# IO4-Turtle.net
KiCad netlist of a schematic drawn in EAGLE
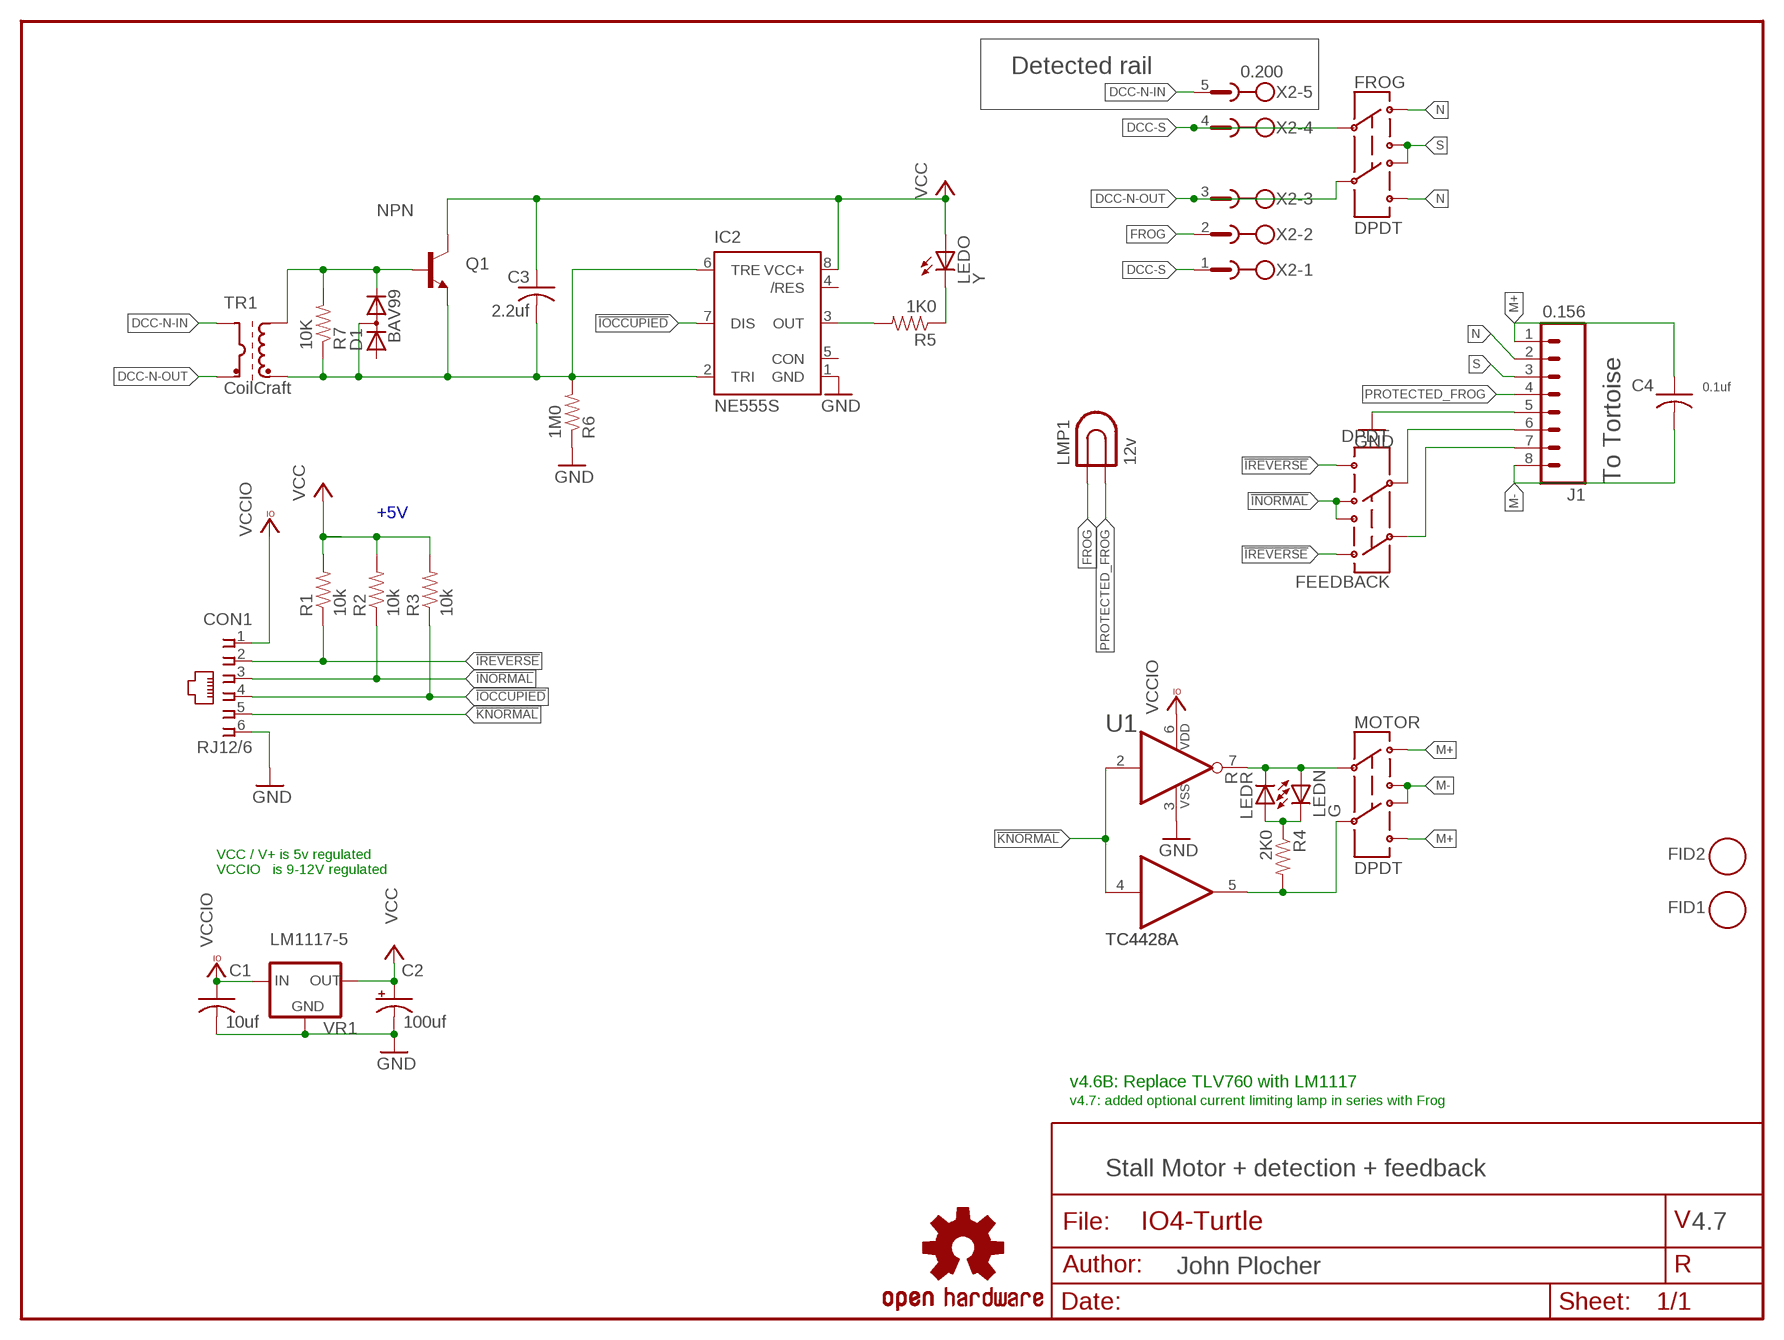
[diagram p0: schematic, sheet 1]

(export (version "E")
  (design (tool "Eeschema 10.0.6"))
  (components
    (comp (ref "C1")
      (value "10uf")
      (footprint "eagle-import:0603-CAP")
      (libsource (lib "eagle-import") (part "CAP0603"))
    )
    (comp (ref "C2")
      (value "100uf")
      (footprint "eagle-import:PANASONIC_D")
      (libsource (lib "eagle-import") (part "CAP-POLD"))
    )
    (comp (ref "C3")
      (value "2.2uf")
      (footprint "eagle-import:0603-CAP")
      (libsource (lib "eagle-import") (part "CAP0603"))
    )
    (comp (ref "C4")
      (value "0.1uf")
      (footprint "eagle-import:0805-CAP")
      (libsource (lib "eagle-import") (part "CAP0805"))
    )
    (comp (ref "CON1")
      (value "RJ12/6")
      (footprint "eagle-import:RJ25-INVERTED")
      (libsource (lib "eagle-import") (part "CONNECTOR-RJ25-43860-2-MOLEX"))
    )
    (comp (ref "D1")
      (value "BAV99")
      (footprint "eagle-import:SOT23")
      (libsource (lib "eagle-import") (part "DIODE-BAV199"))
    )
    (comp (ref "FEEDBACK")
      (value "DPDT")
      (footprint "eagle-import:8X8-SQ-PB")
      (libsource (lib "eagle-import") (part "SWITCH-DPDTPTH-PB"))
    )
    (comp (ref "FID1")
      (value "FIDUCIAL")
      (footprint "eagle-import:FIDUCIAL_1MM")
      (libsource (lib "eagle-import") (part "FIDUCIAL"))
    )
    (comp (ref "FID2")
      (value "FIDUCIAL")
      (footprint "eagle-import:FIDUCIAL_1MM")
      (libsource (lib "eagle-import") (part "FIDUCIAL"))
    )
    (comp (ref "FROG")
      (value "DPDT")
      (footprint "eagle-import:8X8-SQ-PB")
      (libsource (lib "eagle-import") (part "SWITCH-DPDTPTH-PB"))
    )
    (comp (ref "IC1")
      (value "TC4428A")
      (footprint "eagle-import:SO-08")
      (libsource (lib "eagle-import") (part "TC4428ASOICCOA"))
    )
    (comp (ref "IC2")
      (value "NE555S")
      (footprint "eagle-import:SO08")
      (libsource (lib "eagle-import") (part "NE555D"))
    )
    (comp (ref "J1")
      (value "0.156")
      (footprint "eagle-import:KK-156-8-F")
      (libsource (lib "eagle-import") (part "CONNECTOR-M081.56-F"))
    )
    (comp (ref "LEDN")
      (value "G")
      (footprint "eagle-import:0603-LED")
      (libsource (lib "eagle-import") (part "LED0603-LED"))
    )
    (comp (ref "LEDO")
      (value "Y")
      (footprint "eagle-import:0603-LED")
      (libsource (lib "eagle-import") (part "LED0603-LED"))
    )
    (comp (ref "LEDR")
      (value "R")
      (footprint "eagle-import:0603-LED")
      (libsource (lib "eagle-import") (part "LED0603-LED"))
    )
    (comp (ref "LMP1")
      (value "12v")
      (footprint "eagle-import:BULB-3156")
      (libsource (lib "eagle-import") (part "LAMPBULB"))
    )
    (comp (ref "MOTOR")
      (value "DPDT")
      (footprint "eagle-import:8X8-SQ-PB")
      (libsource (lib "eagle-import") (part "SWITCH-DPDTPTH-PB"))
    )
    (comp (ref "OSHW1")
      (value "OSHW")
      (footprint "eagle-import:OSHW-LOGO-M")
      (libsource (lib "eagle-import") (part "DOC-OSHW-LOGO-M"))
    )
    (comp (ref "Q1")
      (value "NPN")
      (footprint "eagle-import:SOT23")
      (libsource (lib "eagle-import") (part "NPN-SOT23"))
    )
    (comp (ref "R1")
      (value "10k")
      (footprint "eagle-import:0603-RES")
      (libsource (lib "eagle-import") (part "R0603-RES"))
    )
    (comp (ref "R2")
      (value "10k")
      (footprint "eagle-import:0603-RES")
      (libsource (lib "eagle-import") (part "R0603-RES"))
    )
    (comp (ref "R3")
      (value "10k")
      (footprint "eagle-import:0603-RES")
      (libsource (lib "eagle-import") (part "R0603-RES"))
    )
    (comp (ref "R4")
      (value "2K0")
      (footprint "eagle-import:0603-RES")
      (libsource (lib "eagle-import") (part "R0603-RES"))
    )
    (comp (ref "R5")
      (value "1K0")
      (footprint "eagle-import:0603-RES")
      (libsource (lib "eagle-import") (part "R0603-RES"))
    )
    (comp (ref "R6")
      (value "1M0")
      (footprint "eagle-import:0603-RES")
      (libsource (lib "eagle-import") (part "R0603-RES"))
    )
    (comp (ref "R7")
      (value "10K")
      (footprint "eagle-import:0603-RES")
      (libsource (lib "eagle-import") (part "R0603-RES"))
    )
    (comp (ref "TR1")
      (value "CoilCraft")
      (footprint "eagle-import:TH-T4")
      (libsource (lib "eagle-import") (part "PULSE-TRANSFORMERPTH"))
    )
    (comp (ref "VR1")
      (value "LM1117-5")
      (footprint "eagle-import:SOT223")
      (libsource (lib "eagle-import") (part "VREG-?-GOI5"))
    )
    (comp (ref "X2")
      (value "0.200")
      (footprint "eagle-import:MSTBA5")
      (fields (field (name "MPN") "1757271"))
      (libsource (lib "eagle-import") (part "MSTBA5"))
    )
  )
  (nets
    (net (code "1") (name "/~{INORMAL}") (class "Default")
      (node (ref "CON1") (pin "3") (pinfunction "3_3") (pintype "passive"))
      (node (ref "FEEDBACK") (pin "1B") (pinfunction "1B_1B") (pintype "bidirectional"))
      (node (ref "FEEDBACK") (pin "2A") (pinfunction "2A_2A") (pintype "bidirectional"))
      (node (ref "R2") (pin "1") (pinfunction "1_1") (pintype "passive"))
    )
    (net (code "2") (name "/~{IOCCUPIED}") (class "Default")
      (node (ref "CON1") (pin "4") (pinfunction "4_4") (pintype "passive"))
      (node (ref "IC2") (pin "7") (pinfunction "DIS_7") (pintype "input"))
      (node (ref "R3") (pin "1") (pinfunction "1_1") (pintype "passive"))
    )
    (net (code "3") (name "/~{IREVERSE}") (class "Default")
      (node (ref "CON1") (pin "2") (pinfunction "2_2") (pintype "passive"))
      (node (ref "FEEDBACK") (pin "1A") (pinfunction "1A_1A") (pintype "bidirectional"))
      (node (ref "FEEDBACK") (pin "2B") (pinfunction "2B_2B") (pintype "bidirectional"))
      (node (ref "R1") (pin "1") (pinfunction "1_1") (pintype "passive"))
    )
    (net (code "4") (name "/~{KNORMAL}") (class "Default")
      (node (ref "CON1") (pin "5") (pinfunction "5_5") (pintype "passive"))
      (node (ref "IC1") (pin "2") (pinfunction "I_2") (pintype "input"))
      (node (ref "IC1") (pin "4") (pinfunction "I_4") (pintype "input"))
    )
    (net (code "5") (name "DCC-N-IN") (class "Default")
      (node (ref "TR1") (pin "P1") (pinfunction "DCC-A_P1") (pintype "passive"))
      (node (ref "X2") (pin "5") (pinfunction "1_5") (pintype "passive"))
    )
    (net (code "6") (name "DCC-N-OUT") (class "Default")
      (node (ref "FROG") (pin "2C") (pinfunction "2C_2C") (pintype "bidirectional"))
      (node (ref "TR1") (pin "P2") (pinfunction "DCC-B_P2") (pintype "passive"))
      (node (ref "X2") (pin "3") (pinfunction "1_3") (pintype "passive"))
    )
    (net (code "7") (name "DCC-S") (class "Default")
      (node (ref "FROG") (pin "1C") (pinfunction "1C_1C") (pintype "bidirectional"))
      (node (ref "X2") (pin "1") (pinfunction "1_1") (pintype "passive"))
      (node (ref "X2") (pin "4") (pinfunction "1_4") (pintype "passive"))
    )
    (net (code "8") (name "FROG") (class "Default")
      (node (ref "LMP1") (pin "P$1") (pinfunction "1_P$1") (pintype "passive"))
      (node (ref "X2") (pin "2") (pinfunction "1_2") (pintype "passive"))
    )
    (net (code "9") (name "GND") (class "Default")
      (node (ref "C1") (pin "2") (pinfunction "2_2") (pintype "passive"))
      (node (ref "C2") (pin "-") (pinfunction "-_-") (pintype "passive"))
      (node (ref "CON1") (pin "6") (pinfunction "6_6") (pintype "passive"))
      (node (ref "IC1") (pin "3") (pinfunction "VSS_3") (pintype "power_in"))
      (node (ref "IC2") (pin "1") (pinfunction "GND_1") (pintype "power_in"))
      (node (ref "J1") (pin "5") (pinfunction "5_5") (pintype "passive"))
      (node (ref "R6") (pin "1") (pinfunction "1_1") (pintype "passive"))
      (node (ref "VR1") (pin "1") (pinfunction "GND_1") (pintype "input"))
    )
    (net (code "10") (name "M+") (class "Default")
      (node (ref "C4") (pin "1") (pinfunction "1_1") (pintype "passive"))
      (node (ref "J1") (pin "1") (pinfunction "1_1") (pintype "passive"))
      (node (ref "MOTOR") (pin "1A") (pinfunction "1A_1A") (pintype "bidirectional"))
      (node (ref "MOTOR") (pin "2B") (pinfunction "2B_2B") (pintype "bidirectional"))
    )
    (net (code "11") (name "M-") (class "Default")
      (node (ref "C4") (pin "2") (pinfunction "2_2") (pintype "passive"))
      (node (ref "J1") (pin "8") (pinfunction "8_8") (pintype "passive"))
      (node (ref "MOTOR") (pin "1B") (pinfunction "1B_1B") (pintype "bidirectional"))
      (node (ref "MOTOR") (pin "2A") (pinfunction "2A_2A") (pintype "bidirectional"))
    )
    (net (code "12") (name "N") (class "Default")
      (node (ref "FROG") (pin "1A") (pinfunction "1A_1A") (pintype "bidirectional"))
      (node (ref "FROG") (pin "2B") (pinfunction "2B_2B") (pintype "bidirectional"))
      (node (ref "J1") (pin "2") (pinfunction "2_2") (pintype "passive"))
    )
    (net (code "13") (name "Net-(D1-AC)") (class "Default")
      (node (ref "C3") (pin "2") (pinfunction "2_2") (pintype "passive"))
      (node (ref "D1") (pin "3") (pinfunction "AC_3") (pintype "passive"))
      (node (ref "IC2") (pin "2") (pinfunction "TRI_2") (pintype "input"))
      (node (ref "IC2") (pin "6") (pinfunction "TRE_6") (pintype "input"))
      (node (ref "Q1") (pin "2") (pinfunction "E_2") (pintype "passive"))
      (node (ref "R6") (pin "2") (pinfunction "2_2") (pintype "passive"))
      (node (ref "R7") (pin "1") (pinfunction "1_1") (pintype "passive"))
      (node (ref "TR1") (pin "S2") (pinfunction "OUT-B_S2") (pintype "passive"))
    )
    (net (code "14") (name "Net-(D1-C)") (class "Default")
      (node (ref "D1") (pin "2") (pinfunction "C_2") (pintype "passive"))
      (node (ref "Q1") (pin "1") (pinfunction "B_1") (pintype "passive"))
      (node (ref "R7") (pin "2") (pinfunction "2_2") (pintype "passive"))
      (node (ref "TR1") (pin "S1") (pinfunction "OUT-A_S1") (pintype "passive"))
    )
    (net (code "15") (name "Net-(FEEDBACK-Pad1C)") (class "Default")
      (node (ref "FEEDBACK") (pin "1C") (pinfunction "1C_1C") (pintype "bidirectional"))
      (node (ref "J1") (pin "7") (pinfunction "7_7") (pintype "passive"))
    )
    (net (code "16") (name "Net-(FEEDBACK-Pad2C)") (class "Default")
      (node (ref "FEEDBACK") (pin "2C") (pinfunction "2C_2C") (pintype "bidirectional"))
      (node (ref "J1") (pin "6") (pinfunction "6_6") (pintype "passive"))
    )
    (net (code "17") (name "Net-(IC1A-O)") (class "Default")
      (node (ref "IC1") (pin "7") (pinfunction "O_7") (pintype "output"))
      (node (ref "LEDN") (pin "A") (pinfunction "A_A") (pintype "passive"))
      (node (ref "LEDR") (pin "C") (pinfunction "C_C") (pintype "passive"))
      (node (ref "MOTOR") (pin "1C") (pinfunction "1C_1C") (pintype "bidirectional"))
    )
    (net (code "18") (name "Net-(IC1C-O)") (class "Default")
      (node (ref "IC1") (pin "5") (pinfunction "O_5") (pintype "output"))
      (node (ref "MOTOR") (pin "2C") (pinfunction "2C_2C") (pintype "bidirectional"))
      (node (ref "R4") (pin "2") (pinfunction "2_2") (pintype "passive"))
    )
    (net (code "19") (name "Net-(IC2-OUT)") (class "Default")
      (node (ref "IC2") (pin "3") (pinfunction "OUT_3") (pintype "output"))
      (node (ref "R5") (pin "2") (pinfunction "2_2") (pintype "passive"))
    )
    (net (code "20") (name "Net-(LEDN-PadC)") (class "Default")
      (node (ref "LEDN") (pin "C") (pinfunction "C_C") (pintype "passive"))
      (node (ref "LEDR") (pin "A") (pinfunction "A_A") (pintype "passive"))
      (node (ref "R4") (pin "1") (pinfunction "1_1") (pintype "passive"))
    )
    (net (code "21") (name "Net-(LEDO-PadC)") (class "Default")
      (node (ref "LEDO") (pin "C") (pinfunction "C_C") (pintype "passive"))
      (node (ref "R5") (pin "1") (pinfunction "1_1") (pintype "passive"))
    )
    (net (code "22") (name "PROTECTED_FROG") (class "Default")
      (node (ref "J1") (pin "4") (pinfunction "4_4") (pintype "passive"))
      (node (ref "LMP1") (pin "P$2") (pinfunction "2_P$2") (pintype "passive"))
    )
    (net (code "23") (name "S") (class "Default")
      (node (ref "FROG") (pin "1B") (pinfunction "1B_1B") (pintype "bidirectional"))
      (node (ref "FROG") (pin "2A") (pinfunction "2A_2A") (pintype "bidirectional"))
      (node (ref "J1") (pin "3") (pinfunction "3_3") (pintype "passive"))
    )
    (net (code "24") (name "VCC") (class "Default")
      (node (ref "C2") (pin "+") (pinfunction "+_+") (pintype "passive"))
      (node (ref "C3") (pin "1") (pinfunction "1_1") (pintype "passive"))
      (node (ref "IC2") (pin "8") (pinfunction "VCC+_8") (pintype "power_in"))
      (node (ref "LEDO") (pin "A") (pinfunction "A_A") (pintype "passive"))
      (node (ref "Q1") (pin "3") (pinfunction "C_3") (pintype "passive"))
      (node (ref "R1") (pin "2") (pinfunction "2_2") (pintype "passive"))
      (node (ref "R2") (pin "2") (pinfunction "2_2") (pintype "passive"))
      (node (ref "R3") (pin "2") (pinfunction "2_2") (pintype "passive"))
      (node (ref "VR1") (pin "2") (pinfunction "OUT_2") (pintype "output"))
      (node (ref "VR1") (pin "4") (pinfunction "OUT_4") (pintype "output"))
    )
    (net (code "25") (name "VCCIO") (class "Default")
      (node (ref "C1") (pin "1") (pinfunction "1_1") (pintype "passive"))
      (node (ref "CON1") (pin "1") (pinfunction "1_1") (pintype "passive"))
      (node (ref "IC1") (pin "6") (pinfunction "VDD_6") (pintype "power_in"))
      (node (ref "VR1") (pin "3") (pinfunction "IN_3") (pintype "input"))
    )
    (net (code "26") (name "unconnected-(D1-A-Pad1)") (class "Default")
      (node (ref "D1") (pin "1") (pinfunction "A_1") (pintype "passive"))
    )
    (net (code "27") (name "unconnected-(IC2-CON-Pad5)") (class "Default")
      (node (ref "IC2") (pin "5") (pinfunction "CON_5") (pintype "input"))
    )
    (net (code "28") (name "unconnected-(IC2-{slash}RES-Pad4)") (class "Default")
      (node (ref "IC2") (pin "4") (pinfunction "/RES_4") (pintype "input"))
    )
  )
)
